# OLED_BREAKOUT.net
KiCad netlist of a schematic drawn in Altium Designer
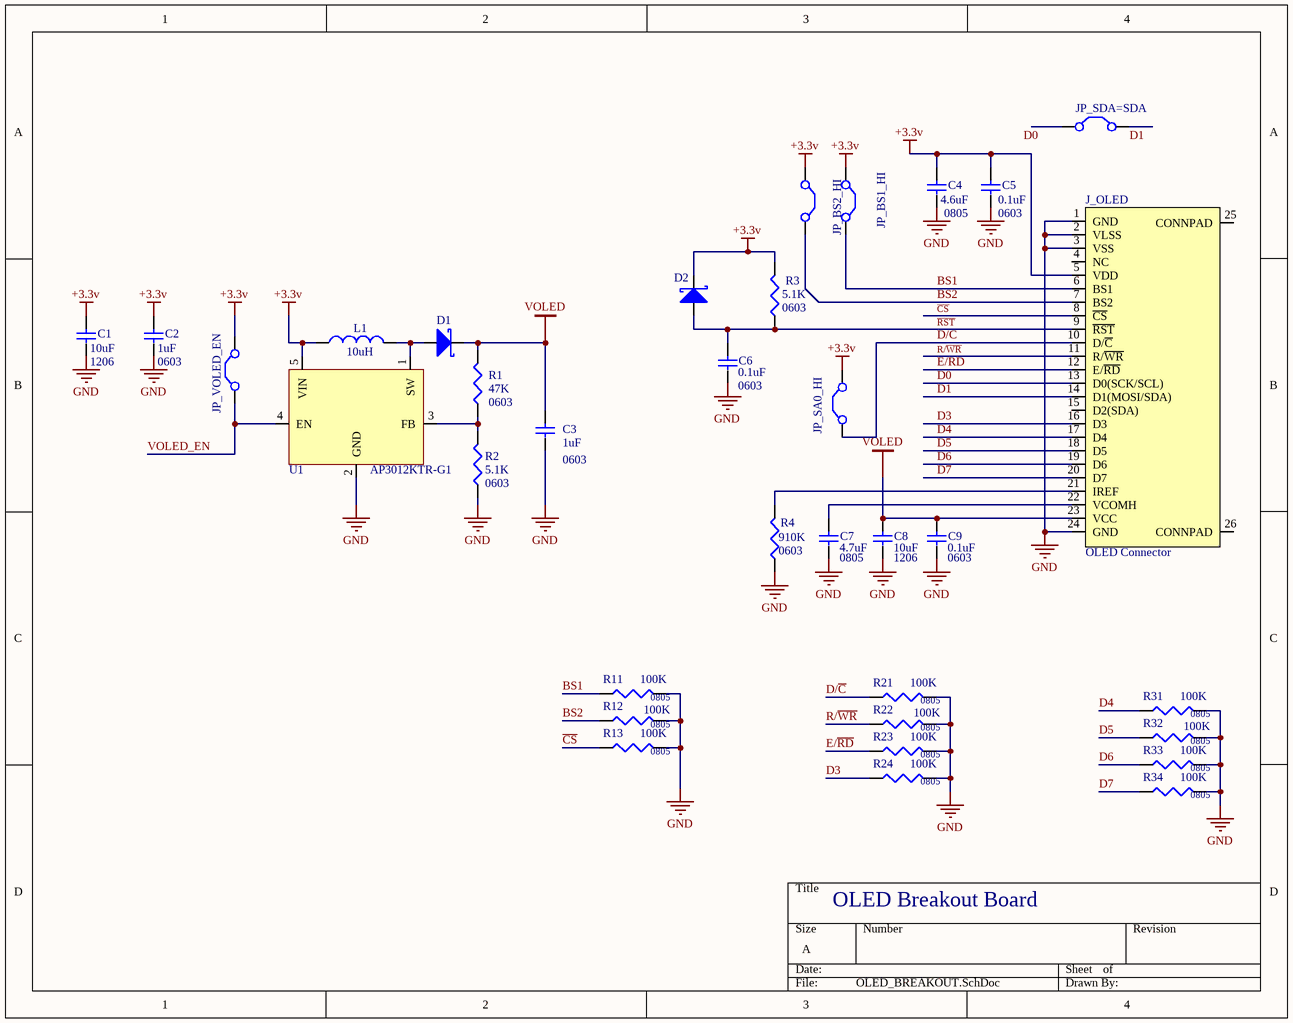
[diagram p0: OLED_BREAKOUT.SchDoc]

(export (version "E")
  (design (tool "Eeschema 10.0.6"))
  (components
    (comp (ref "C1")
      (value "Capacitor")
      (footprint "SMD-1206")
      (fields (field (name "CAPACTIANCE") "10uF") (field (name "SIZE") "1206"))
      (libsource (lib "OLED_BREAKOUT_SCH_LIB") (part "Capacitor"))
    )
    (comp (ref "C2")
      (value "Capacitor")
      (footprint "SMD-0603")
      (fields (field (name "CAPACITANCE") "1uF") (field (name "SIZE") "0603"))
      (libsource (lib "OLED_BREAKOUT_SCH_LIB") (part "Capacitor"))
    )
    (comp (ref "C3")
      (value "Capacitor")
      (footprint "SMD-0603")
      (fields (field (name "CAPACITANCE") "1uF") (field (name "SIZE") "0603"))
      (libsource (lib "OLED_BREAKOUT_SCH_LIB") (part "Capacitor"))
    )
    (comp (ref "C4")
      (value "Capacitor")
      (footprint "SMD-0805")
      (fields (field (name "CAPACITANCE") "4.6uF") (field (name "SIZE") "0805"))
      (libsource (lib "OLED_BREAKOUT_SCH_LIB") (part "Capacitor"))
    )
    (comp (ref "C5")
      (value "Capacitor")
      (footprint "SMD-0603")
      (fields (field (name "CAPACITANCE") "0.1uF") (field (name "SIZE") "0603"))
      (libsource (lib "OLED_BREAKOUT_SCH_LIB") (part "Capacitor"))
    )
    (comp (ref "C6")
      (value "Capacitor")
      (footprint "SMD-0603")
      (fields (field (name "CAPACITANCE") "0.1uF") (field (name "SIZE") "0603"))
      (libsource (lib "OLED_BREAKOUT_SCH_LIB") (part "Capacitor"))
    )
    (comp (ref "C7")
      (value "Capacitor")
      (footprint "SMD-0805")
      (fields (field (name "CAPACITANCE") "4.7uF") (field (name "SIZE") "0805"))
      (libsource (lib "OLED_BREAKOUT_SCH_LIB") (part "Capacitor"))
    )
    (comp (ref "C8")
      (value "Capacitor")
      (footprint "SMD-1206")
      (fields (field (name "CAPACITANCE") "10uF") (field (name "SIZE") "1206"))
      (libsource (lib "OLED_BREAKOUT_SCH_LIB") (part "Capacitor"))
    )
    (comp (ref "C9")
      (value "Capacitor")
      (footprint "SMD-0603")
      (fields (field (name "CAPACITANCE") "0.1uF") (field (name "SIZE") "0603"))
      (libsource (lib "OLED_BREAKOUT_SCH_LIB") (part "Capacitor"))
    )
    (comp (ref "D1")
      (value "Diode Schottky")
      (footprint "D1_SOD-123")
      (libsource (lib "OLED_BREAKOUT_SCH_LIB") (part "Diode Schottky"))
    )
    (comp (ref "D2")
      (value "Diode Schottky")
      (footprint "D2_SOD523")
      (libsource (lib "OLED_BREAKOUT_SCH_LIB") (part "Diode Schottky"))
    )
    (comp (ref "JP_BS1_HI")
      (value "Jumper")
      (footprint "SMD-0805")
      (description "Jumper Wire")
      (fields (field (name "PUBLISHER") "Altium Limited"))
      (libsource (lib "Miscellaneous Devices") (part "Jumper"))
    )
    (comp (ref "JP_BS2_HI")
      (value "Jumper")
      (footprint "SMD-0805")
      (description "Jumper Wire")
      (fields (field (name "PUBLISHER") "Altium Limited"))
      (libsource (lib "Miscellaneous Devices") (part "Jumper"))
    )
    (comp (ref "JP_SA0_HI")
      (value "Jumper")
      (footprint "SMD-0805")
      (description "Jumper Wire")
      (fields (field (name "PUBLISHER") "Altium Limited"))
      (libsource (lib "Miscellaneous Devices") (part "Jumper"))
    )
    (comp (ref "JP_SDA=SDA")
      (value "Jumper")
      (footprint "SMD-0805")
      (description "Jumper Wire")
      (fields (field (name "PUBLISHER") "Altium Limited"))
      (libsource (lib "Miscellaneous Devices") (part "Jumper"))
    )
    (comp (ref "JP_VOLED_EN")
      (value "Jumper")
      (footprint "SMD-0805")
      (description "Jumper Wire")
      (fields (field (name "PUBLISHER") "Altium Limited"))
      (libsource (lib "Miscellaneous Devices") (part "Jumper"))
    )
    (comp (ref "J_OLED")
      (value "OLED Connector")
      (footprint "J_OLED")
      (description "24 Position, 0.5mm Pitch, Gold, FCC FPC ZIF Connector")
      (libsource (lib "OLED_BREAKOUT_SCH_LIB") (part "OLED Connector"))
    )
    (comp (ref "L1")
      (value "Inductor")
      (footprint "L1")
      (fields (field (name "INDUCTANCE") "10uH"))
      (libsource (lib "OLED_BREAKOUT_SCH_LIB") (part "Inductor"))
    )
    (comp (ref "R1")
      (value "Resistor")
      (footprint "SMD-0603")
      (fields (field (name "RESISTANCE") "47K") (field (name "SIZE") "0603"))
      (libsource (lib "OLED_BREAKOUT_SCH_LIB") (part "Resistor"))
    )
    (comp (ref "R2")
      (value "Resistor")
      (footprint "SMD-0603")
      (fields (field (name "RESISTANCE") "5.1K") (field (name "SIZE") "0603"))
      (libsource (lib "OLED_BREAKOUT_SCH_LIB") (part "Resistor"))
    )
    (comp (ref "R3")
      (value "Resistor")
      (footprint "SMD-0603")
      (fields (field (name "RESISTANCE") "5.1K") (field (name "SIZE") "0603"))
      (libsource (lib "OLED_BREAKOUT_SCH_LIB") (part "Resistor"))
    )
    (comp (ref "R4")
      (value "Resistor")
      (footprint "SMD-0603")
      (fields (field (name "RESISTANCE") "910K") (field (name "SIZE") "0603"))
      (libsource (lib "OLED_BREAKOUT_SCH_LIB") (part "Resistor"))
    )
    (comp (ref "R11")
      (value "Resistor")
      (footprint "SMD-0805")
      (fields (field (name "RESISTANCE") "100K") (field (name "SIZE") "0805"))
      (libsource (lib "OLED_BREAKOUT_SCH_LIB") (part "Resistor"))
    )
    (comp (ref "R12")
      (value "Resistor")
      (footprint "SMD-0805")
      (fields (field (name "RESISTANCE") "100K") (field (name "SIZE") "0805"))
      (libsource (lib "OLED_BREAKOUT_SCH_LIB") (part "Resistor"))
    )
    (comp (ref "R13")
      (value "Resistor")
      (footprint "SMD-0805")
      (fields (field (name "RESISTANCE") "100K") (field (name "SIZE") "0805"))
      (libsource (lib "OLED_BREAKOUT_SCH_LIB") (part "Resistor"))
    )
    (comp (ref "R21")
      (value "Resistor")
      (footprint "SMD-0805")
      (fields (field (name "RESISTANCE") "100K") (field (name "SIZE") "0805"))
      (libsource (lib "OLED_BREAKOUT_SCH_LIB") (part "Resistor"))
    )
    (comp (ref "R22")
      (value "Resistor")
      (footprint "SMD-0805")
      (fields (field (name "RESISTANCE") "100K") (field (name "SIZE") "0805"))
      (libsource (lib "OLED_BREAKOUT_SCH_LIB") (part "Resistor"))
    )
    (comp (ref "R23")
      (value "Resistor")
      (footprint "SMD-0805")
      (fields (field (name "RESISTANCE") "100K") (field (name "SIZE") "0805"))
      (libsource (lib "OLED_BREAKOUT_SCH_LIB") (part "Resistor"))
    )
    (comp (ref "R24")
      (value "Resistor")
      (footprint "SMD-0805")
      (fields (field (name "RESISTANCE") "100K") (field (name "SIZE") "0805"))
      (libsource (lib "OLED_BREAKOUT_SCH_LIB") (part "Resistor"))
    )
    (comp (ref "R31")
      (value "Resistor")
      (footprint "SMD-0805")
      (fields (field (name "RESISTANCE") "100K") (field (name "SIZE") "0805"))
      (libsource (lib "OLED_BREAKOUT_SCH_LIB") (part "Resistor"))
    )
    (comp (ref "R32")
      (value "Resistor")
      (footprint "SMD-0805")
      (fields (field (name "RESISTANCE") "100K") (field (name "SIZE") "0805"))
      (libsource (lib "OLED_BREAKOUT_SCH_LIB") (part "Resistor"))
    )
    (comp (ref "R33")
      (value "Resistor")
      (footprint "SMD-0805")
      (fields (field (name "RESISTANCE") "100K") (field (name "SIZE") "0805"))
      (libsource (lib "OLED_BREAKOUT_SCH_LIB") (part "Resistor"))
    )
    (comp (ref "R34")
      (value "Resistor")
      (footprint "SMD-0805")
      (fields (field (name "RESISTANCE") "100K") (field (name "SIZE") "0805"))
      (libsource (lib "OLED_BREAKOUT_SCH_LIB") (part "Resistor"))
    )
    (comp (ref "U1")
      (value "DC/DC Voltage Regulator")
      (footprint "U1_SOT-23-5")
      (description "Integrated Circuits (ICs)\nPMIC - Voltage Regulators - DC DC Switching Regulators")
      (fields (field (name "PART#") "AP3012KTR-G1"))
      (libsource (lib "OLED_BREAKOUT_SCH_LIB") (part "DC/DC Voltage Regulator"))
    )
  )
  (nets
    (net (code "1") (name "+3.3v") (class "Default")
      (node (ref "C1") (pin "2") (pinfunction "2_2") (pintype "passive"))
      (node (ref "C2") (pin "2") (pinfunction "2_2") (pintype "passive"))
      (node (ref "C4") (pin "2") (pinfunction "2_2") (pintype "passive"))
      (node (ref "C5") (pin "2") (pinfunction "2_2") (pintype "passive"))
      (node (ref "D2") (pin "2") (pinfunction "2_2") (pintype "passive"))
      (node (ref "JP_BS1_HI") (pin "1") (pinfunction "C1_1") (pintype "passive"))
      (node (ref "JP_BS2_HI") (pin "1") (pinfunction "C1_1") (pintype "passive"))
      (node (ref "JP_SA0_HI") (pin "2") (pinfunction "C2_2") (pintype "passive"))
      (node (ref "JP_VOLED_EN") (pin "2") (pinfunction "C2_2") (pintype "passive"))
      (node (ref "J_OLED") (pin "5") (pinfunction "VDD_5") (pintype "passive"))
      (node (ref "L1") (pin "1") (pinfunction "1_1") (pintype "passive"))
      (node (ref "R3") (pin "2") (pinfunction "2_2") (pintype "passive"))
      (node (ref "U1") (pin "5") (pinfunction "VIN_5") (pintype "passive"))
    )
    (net (code "2") (name "/BS1") (class "Default")
      (node (ref "JP_BS1_HI") (pin "2") (pinfunction "C2_2") (pintype "passive"))
      (node (ref "J_OLED") (pin "6") (pinfunction "BS1_6") (pintype "passive"))
      (node (ref "R11") (pin "1") (pinfunction "1_1") (pintype "passive"))
    )
    (net (code "3") (name "/BS2") (class "Default")
      (node (ref "JP_BS2_HI") (pin "2") (pinfunction "C2_2") (pintype "passive"))
      (node (ref "J_OLED") (pin "7") (pinfunction "BS2_7") (pintype "passive"))
      (node (ref "R12") (pin "1") (pinfunction "1_1") (pintype "passive"))
    )
    (net (code "4") (name "/D0") (class "Default")
      (node (ref "JP_SDA=SDA") (pin "1") (pinfunction "C1_1") (pintype "passive"))
      (node (ref "J_OLED") (pin "13") (pinfunction "D0(SCK/SCL)_13") (pintype "passive"))
    )
    (net (code "5") (name "/D1") (class "Default")
      (node (ref "JP_SDA=SDA") (pin "2") (pinfunction "C2_2") (pintype "passive"))
      (node (ref "J_OLED") (pin "14") (pinfunction "D1(MOSI/SDA)_14") (pintype "passive"))
    )
    (net (code "6") (name "/D3") (class "Default")
      (node (ref "J_OLED") (pin "16") (pinfunction "D3_16") (pintype "passive"))
      (node (ref "R24") (pin "1") (pinfunction "1_1") (pintype "passive"))
    )
    (net (code "7") (name "/D4") (class "Default")
      (node (ref "J_OLED") (pin "17") (pinfunction "D4_17") (pintype "passive"))
      (node (ref "R31") (pin "1") (pinfunction "1_1") (pintype "passive"))
    )
    (net (code "8") (name "/D5") (class "Default")
      (node (ref "J_OLED") (pin "18") (pinfunction "D5_18") (pintype "passive"))
      (node (ref "R32") (pin "1") (pinfunction "1_1") (pintype "passive"))
    )
    (net (code "9") (name "/D6") (class "Default")
      (node (ref "J_OLED") (pin "19") (pinfunction "D6_19") (pintype "passive"))
      (node (ref "R33") (pin "1") (pinfunction "1_1") (pintype "passive"))
    )
    (net (code "10") (name "/D7") (class "Default")
      (node (ref "J_OLED") (pin "20") (pinfunction "D7_20") (pintype "passive"))
      (node (ref "R34") (pin "1") (pinfunction "1_1") (pintype "passive"))
    )
    (net (code "11") (name "/D{slash}~{C}") (class "Default")
      (node (ref "JP_SA0_HI") (pin "1") (pinfunction "C1_1") (pintype "passive"))
      (node (ref "J_OLED") (pin "10") (pinfunction "D/~{C}_10") (pintype "passive"))
      (node (ref "R21") (pin "1") (pinfunction "1_1") (pintype "passive"))
    )
    (net (code "12") (name "/E{slash}~{RD}") (class "Default")
      (node (ref "J_OLED") (pin "12") (pinfunction "E/~{RD}_12") (pintype "passive"))
      (node (ref "R23") (pin "1") (pinfunction "1_1") (pintype "passive"))
    )
    (net (code "13") (name "/R{slash}~{WR}") (class "Default")
      (node (ref "J_OLED") (pin "11") (pinfunction "R/~{WR}_11") (pintype "passive"))
      (node (ref "R22") (pin "1") (pinfunction "1_1") (pintype "passive"))
    )
    (net (code "14") (name "/VOLED_EN") (class "Default")
      (node (ref "JP_VOLED_EN") (pin "1") (pinfunction "C1_1") (pintype "passive"))
      (node (ref "U1") (pin "4") (pinfunction "EN_4") (pintype "passive"))
    )
    (net (code "15") (name "/~{CS}") (class "Default")
      (node (ref "J_OLED") (pin "8") (pinfunction "~{CS}_8") (pintype "passive"))
      (node (ref "R13") (pin "1") (pinfunction "1_1") (pintype "passive"))
    )
    (net (code "16") (name "/~{RST}") (class "Default")
      (node (ref "C6") (pin "2") (pinfunction "2_2") (pintype "passive"))
      (node (ref "D2") (pin "1") (pinfunction "1_1") (pintype "passive"))
      (node (ref "J_OLED") (pin "9") (pinfunction "~{RST}_9") (pintype "passive"))
      (node (ref "R3") (pin "1") (pinfunction "1_1") (pintype "passive"))
    )
    (net (code "17") (name "GND") (class "Default")
      (node (ref "C1") (pin "1") (pinfunction "1_1") (pintype "passive"))
      (node (ref "C2") (pin "1") (pinfunction "1_1") (pintype "passive"))
      (node (ref "C3") (pin "1") (pinfunction "1_1") (pintype "passive"))
      (node (ref "C4") (pin "1") (pinfunction "1_1") (pintype "passive"))
      (node (ref "C5") (pin "1") (pinfunction "1_1") (pintype "passive"))
      (node (ref "C6") (pin "1") (pinfunction "1_1") (pintype "passive"))
      (node (ref "C7") (pin "1") (pinfunction "1_1") (pintype "passive"))
      (node (ref "C8") (pin "1") (pinfunction "1_1") (pintype "passive"))
      (node (ref "C9") (pin "1") (pinfunction "1_1") (pintype "passive"))
      (node (ref "J_OLED") (pin "1") (pinfunction "GND_1") (pintype "passive"))
      (node (ref "J_OLED") (pin "2") (pinfunction "VLSS_2") (pintype "passive"))
      (node (ref "J_OLED") (pin "24") (pinfunction "GND_24") (pintype "passive"))
      (node (ref "J_OLED") (pin "3") (pinfunction "VSS_3") (pintype "passive"))
      (node (ref "R11") (pin "2") (pinfunction "2_2") (pintype "passive"))
      (node (ref "R12") (pin "2") (pinfunction "2_2") (pintype "passive"))
      (node (ref "R13") (pin "2") (pinfunction "2_2") (pintype "passive"))
      (node (ref "R2") (pin "1") (pinfunction "1_1") (pintype "passive"))
      (node (ref "R21") (pin "2") (pinfunction "2_2") (pintype "passive"))
      (node (ref "R22") (pin "2") (pinfunction "2_2") (pintype "passive"))
      (node (ref "R23") (pin "2") (pinfunction "2_2") (pintype "passive"))
      (node (ref "R24") (pin "2") (pinfunction "2_2") (pintype "passive"))
      (node (ref "R31") (pin "2") (pinfunction "2_2") (pintype "passive"))
      (node (ref "R32") (pin "2") (pinfunction "2_2") (pintype "passive"))
      (node (ref "R33") (pin "2") (pinfunction "2_2") (pintype "passive"))
      (node (ref "R34") (pin "2") (pinfunction "2_2") (pintype "passive"))
      (node (ref "R4") (pin "1") (pinfunction "1_1") (pintype "passive"))
      (node (ref "U1") (pin "2") (pinfunction "GND_2") (pintype "passive"))
    )
    (net (code "18") (name "Net-(J_OLED-IREF)") (class "Default")
      (node (ref "J_OLED") (pin "21") (pinfunction "IREF_21") (pintype "passive"))
      (node (ref "R4") (pin "2") (pinfunction "2_2") (pintype "passive"))
    )
    (net (code "19") (name "Net-(J_OLED-VCOMH)") (class "Default")
      (node (ref "C7") (pin "2") (pinfunction "2_2") (pintype "passive"))
      (node (ref "J_OLED") (pin "22") (pinfunction "VCOMH_22") (pintype "passive"))
    )
    (net (code "20") (name "Net-(U1-FB)") (class "Default")
      (node (ref "R1") (pin "1") (pinfunction "1_1") (pintype "passive"))
      (node (ref "R2") (pin "2") (pinfunction "2_2") (pintype "passive"))
      (node (ref "U1") (pin "3") (pinfunction "FB_3") (pintype "passive"))
    )
    (net (code "21") (name "Net-(U1-SW)") (class "Default")
      (node (ref "D1") (pin "1") (pinfunction "1_1") (pintype "passive"))
      (node (ref "L1") (pin "2") (pinfunction "2_2") (pintype "passive"))
      (node (ref "U1") (pin "1") (pinfunction "SW_1") (pintype "passive"))
    )
    (net (code "22") (name "VOLED") (class "Default")
      (node (ref "C3") (pin "2") (pinfunction "2_2") (pintype "passive"))
      (node (ref "C8") (pin "2") (pinfunction "2_2") (pintype "passive"))
      (node (ref "C9") (pin "2") (pinfunction "2_2") (pintype "passive"))
      (node (ref "D1") (pin "2") (pinfunction "2_2") (pintype "passive"))
      (node (ref "J_OLED") (pin "23") (pinfunction "VCC_23") (pintype "passive"))
      (node (ref "R1") (pin "2") (pinfunction "2_2") (pintype "passive"))
    )
    (net (code "23") (name "unconnected-(J_OLED-CONNPAD-Pad25)") (class "Default")
      (node (ref "J_OLED") (pin "25") (pinfunction "CONNPAD_25") (pintype "passive"))
    )
    (net (code "24") (name "unconnected-(J_OLED-CONNPAD-Pad26)") (class "Default")
      (node (ref "J_OLED") (pin "26") (pinfunction "CONNPAD_26") (pintype "passive"))
    )
    (net (code "25") (name "unconnected-(J_OLED-D2(SDA)-Pad15)") (class "Default")
      (node (ref "J_OLED") (pin "15") (pinfunction "D2(SDA)_15") (pintype "passive"))
    )
    (net (code "26") (name "unconnected-(J_OLED-NC-Pad4)") (class "Default")
      (node (ref "J_OLED") (pin "4") (pinfunction "NC_4") (pintype "passive"))
    )
  )
)
